# V2_0_1_KMX_Switch.net
KiCad netlist of a schematic drawn in EasyEDA Pro
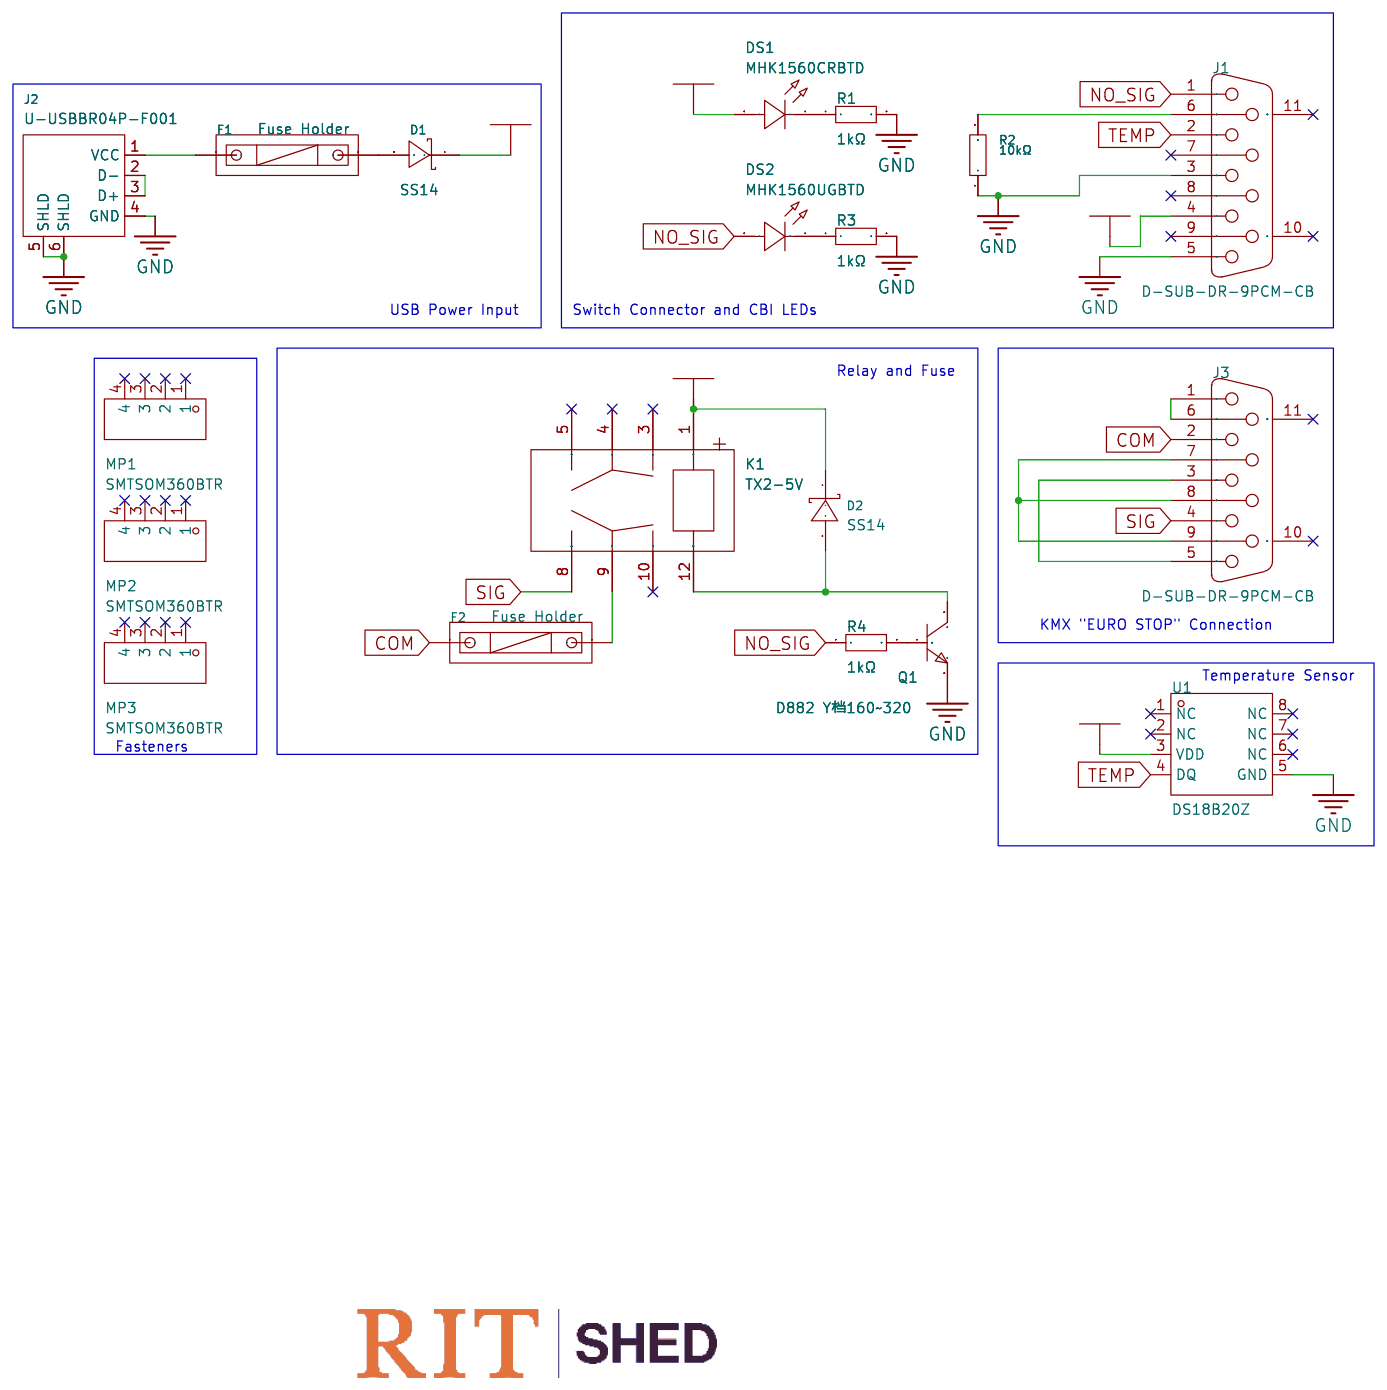
[diagram p0: schematic sheet]

(export (version "E")
  (design (tool "Eeschema 10.0.6"))
  (components
    (comp (ref "D1")
      (value "SS14")
      (footprint "easyedapro:SMA_L4.2-W2.6-LS5.3-RD")
      (fields (field (name "Manufacturer") "MDD"))
      (libsource (lib "easyedapro") (part "SS14"))
    )
    (comp (ref "D2")
      (value "SS14")
      (footprint "easyedapro:SMA_L4.2-W2.6-LS5.3-RD")
      (fields (field (name "Manufacturer") "MDD"))
      (libsource (lib "easyedapro") (part "SS14"))
    )
    (comp (ref "DS1")
      (value "MHK1560CRBTD")
      (footprint "easyedapro:LED-TH_MHK1560UGBTD")
      (fields (field (name "Manufacturer") "MEIHUA(美华)"))
      (libsource (lib "easyedapro") (part "MHK1560CGBTD"))
    )
    (comp (ref "DS2")
      (value "MHK1560UGBTD")
      (footprint "easyedapro:LED-TH_MHK1560UGBTD")
      (fields (field (name "Manufacturer") "MEIHUA(美华)"))
      (libsource (lib "easyedapro") (part "MHK1560UGBTD"))
    )
    (comp (ref "F1")
      (value "Fuse Holder")
      (footprint "easyedapro:FUSE-TH_L24.5-W9.8-P22.5")
      (description "Fuseholder Type:- Fuse Type:- Fuse Size:-")
      (fields (field (name "Manufacturer Part") "保险丝透明座") (field (name "Manufacturer") "xcfuse(旭程)"))
      (libsource (lib "easyedapro") (part "Fuse transparent seat"))
    )
    (comp (ref "F2")
      (value "Fuse Holder")
      (footprint "easyedapro:FUSE-TH_L24.5-W9.8-P22.5")
      (description "Fuseholder Type:- Fuse Type:- Fuse Size:-")
      (fields (field (name "Manufacturer Part") "保险丝透明座") (field (name "Manufacturer") "xcfuse(旭程)"))
      (libsource (lib "easyedapro") (part "Fuse transparent seat"))
    )
    (comp (ref "J1")
      (value "D-SUB-DR-9PCM-CB")
      (footprint "easyedapro:DB9-TH_ID09S33E4GV00LF")
      (fields (field (name "Manufacturer") "XUNPU(讯普)"))
      (libsource (lib "easyedapro") (part "D-SUB-DR-9PCM-CB"))
    )
    (comp (ref "J2")
      (value "U-USBBR04P-F001")
      (footprint "easyedapro:USB-B-TH_U241-041N-1BR85-1")
      (fields (field (name "Manufacturer") "Ckmtw(灿科盟)"))
      (libsource (lib "easyedapro") (part "U-USBBR04P-F001"))
    )
    (comp (ref "J3")
      (value "D-SUB-DR-9PCM-CB")
      (footprint "easyedapro:DB9-TH_ID09S33E4GV00LF")
      (fields (field (name "Manufacturer") "XUNPU(讯普)"))
      (libsource (lib "easyedapro") (part "D-SUB-DR-9PCM-CB"))
    )
    (comp (ref "K1")
      (value "TX2-5V")
      (footprint "easyedapro:RELAY-TH_TX2-3V")
      (fields (field (name "Manufacturer") "PANASONIC(松下)"))
      (libsource (lib "easyedapro") (part "TX2-5V"))
    )
    (comp (ref "MP1")
      (value "SMTSOM360BTR")
      (footprint "easyedapro:SMD_BD5.6-D4.1")
      (fields (field (name "Manufacturer") "YIYUAN(怡远)"))
      (libsource (lib "easyedapro") (part "SMTSOM360BTR"))
    )
    (comp (ref "MP2")
      (value "SMTSOM360BTR")
      (footprint "easyedapro:SMD_BD5.6-D4.1")
      (fields (field (name "Manufacturer") "YIYUAN(怡远)"))
      (libsource (lib "easyedapro") (part "SMTSOM360BTR"))
    )
    (comp (ref "MP3")
      (value "SMTSOM360BTR")
      (footprint "easyedapro:SMD_BD5.6-D4.1")
      (fields (field (name "Manufacturer") "YIYUAN(怡远)"))
      (libsource (lib "easyedapro") (part "SMTSOM360BTR"))
    )
    (comp (ref "Q1")
      (value "D882 Y档160~320")
      (footprint "easyedapro:SOT-89-3_L4.5-W2.5-P1.50-LS4.2-BR")
      (fields (field (name "Manufacturer") "CJ(江苏长电/长晶)"))
      (libsource (lib "easyedapro") (part "D882_C9634"))
    )
    (comp (ref "R1")
      (value "1kΩ")
      (footprint "easyedapro:R0805")
      (fields
        (field (name "Manufacturer Part") "0805W8F1001T5E")
        (field (name "Manufacturer") "UNI-ROYAL(厚声)")
      )
      (libsource (lib "easyedapro") (part "0805W8F1001T5E"))
    )
    (comp (ref "R2")
      (value "10kΩ")
      (footprint "easyedapro:R0805")
      (fields
        (field (name "Manufacturer Part") "0805W8F1002T5E")
        (field (name "Manufacturer") "UNI-ROYAL(厚声)")
      )
      (libsource (lib "easyedapro") (part "0805W8F1002T5E"))
    )
    (comp (ref "R3")
      (value "1kΩ")
      (footprint "easyedapro:R0805")
      (fields
        (field (name "Manufacturer Part") "0805W8F1001T5E")
        (field (name "Manufacturer") "UNI-ROYAL(厚声)")
      )
      (libsource (lib "easyedapro") (part "0805W8F1001T5E"))
    )
    (comp (ref "R4")
      (value "1kΩ")
      (footprint "easyedapro:R0805")
      (fields
        (field (name "Manufacturer Part") "0805W8F1001T5E")
        (field (name "Manufacturer") "UNI-ROYAL(厚声)")
      )
      (libsource (lib "easyedapro") (part "0805W8F1001T5E"))
    )
    (comp (ref "U1")
      (value "DS18B20Z")
      (footprint "easyedapro:SOP-8_L4.9-W3.9-P1.27-LS6.0-BL")
      (description "Resolution:±0.4°C Resolution:±0.4°C Supply Voltage:2.5V~5.5V Supply Voltage:2.5V~5.5V")
      (fields (field (name "Manufacturer") "UMW(友台半导体)"))
      (libsource (lib "easyedapro") (part "DS18B20Z"))
    )
  )
  (nets
    (net (code "1") (name "COM") (class "Default")
      (node (ref "F2") (pin "1") (pinfunction "1_1") (pintype "input"))
      (node (ref "J3") (pin "2") (pinfunction "2_2") (pintype "input"))
    )
    (net (code "2") (name "GND") (class "Default")
      (node (ref "J1") (pin "3") (pinfunction "3_3") (pintype "input"))
      (node (ref "J1") (pin "5") (pinfunction "5_5") (pintype "input"))
      (node (ref "J2") (pin "4") (pinfunction "GND_4") (pintype "input"))
      (node (ref "J2") (pin "5") (pinfunction "SHLD_5") (pintype "input"))
      (node (ref "J2") (pin "6") (pinfunction "SHLD_6") (pintype "input"))
      (node (ref "Q1") (pin "3") (pinfunction "E_3") (pintype "input"))
      (node (ref "R1") (pin "2") (pinfunction "2_2") (pintype "input"))
      (node (ref "R2") (pin "1") (pinfunction "1_1") (pintype "input"))
      (node (ref "R3") (pin "2") (pinfunction "2_2") (pintype "input"))
      (node (ref "U1") (pin "5") (pinfunction "GND_5") (pintype "unspecified"))
    )
    (net (code "3") (name "NO_SIG") (class "Default")
      (node (ref "DS2") (pin "2") (pinfunction "A_2") (pintype "unspecified"))
      (node (ref "J1") (pin "1") (pinfunction "1_1") (pintype "input"))
      (node (ref "R4") (pin "1") (pinfunction "1_1") (pintype "input"))
    )
    (net (code "4") (name "Net-(D1-A)") (class "Default")
      (node (ref "D1") (pin "2") (pinfunction "A_2") (pintype "input"))
      (node (ref "F1") (pin "2") (pinfunction "2_2") (pintype "input"))
    )
    (net (code "5") (name "Net-(D2-A)") (class "Default")
      (node (ref "D2") (pin "2") (pinfunction "A_2") (pintype "input"))
      (node (ref "K1") (pin "12") (pinfunction "12_12") (pintype "input"))
      (node (ref "Q1") (pin "2") (pinfunction "C_2") (pintype "input"))
    )
    (net (code "6") (name "Net-(DS1-K)") (class "Default")
      (node (ref "DS1") (pin "1") (pinfunction "K_1") (pintype "unspecified"))
      (node (ref "R1") (pin "1") (pinfunction "1_1") (pintype "input"))
    )
    (net (code "7") (name "Net-(DS2-K)") (class "Default")
      (node (ref "DS2") (pin "1") (pinfunction "K_1") (pintype "unspecified"))
      (node (ref "R3") (pin "1") (pinfunction "1_1") (pintype "input"))
    )
    (net (code "8") (name "Net-(F2-Pad2)") (class "Default")
      (node (ref "F2") (pin "2") (pinfunction "2_2") (pintype "input"))
      (node (ref "K1") (pin "9") (pinfunction "9_9") (pintype "input"))
    )
    (net (code "9") (name "Net-(J1-Pad6)") (class "Default")
      (node (ref "J1") (pin "6") (pinfunction "6_6") (pintype "input"))
      (node (ref "R2") (pin "2") (pinfunction "2_2") (pintype "input"))
    )
    (net (code "10") (name "Net-(J2-D+)") (class "Default")
      (node (ref "J2") (pin "2") (pinfunction "D-_2") (pintype "input"))
      (node (ref "J2") (pin "3") (pinfunction "D+_3") (pintype "input"))
    )
    (net (code "11") (name "Net-(J2-VCC)") (class "Default")
      (node (ref "F1") (pin "1") (pinfunction "1_1") (pintype "input"))
      (node (ref "J2") (pin "1") (pinfunction "VCC_1") (pintype "input"))
    )
    (net (code "12") (name "Net-(J3-Pad1)") (class "Default")
      (node (ref "J3") (pin "1") (pinfunction "1_1") (pintype "input"))
      (node (ref "J3") (pin "6") (pinfunction "6_6") (pintype "input"))
    )
    (net (code "13") (name "Net-(J3-Pad3)") (class "Default")
      (node (ref "J3") (pin "3") (pinfunction "3_3") (pintype "input"))
      (node (ref "J3") (pin "5") (pinfunction "5_5") (pintype "input"))
    )
    (net (code "14") (name "Net-(J3-Pad7)") (class "Default")
      (node (ref "J3") (pin "7") (pinfunction "7_7") (pintype "input"))
      (node (ref "J3") (pin "8") (pinfunction "8_8") (pintype "input"))
      (node (ref "J3") (pin "9") (pinfunction "9_9") (pintype "input"))
    )
    (net (code "15") (name "Net-(Q1-B)") (class "Default")
      (node (ref "Q1") (pin "1") (pinfunction "B_1") (pintype "input"))
      (node (ref "R4") (pin "2") (pinfunction "2_2") (pintype "input"))
    )
    (net (code "16") (name "SIG") (class "Default")
      (node (ref "J3") (pin "4") (pinfunction "4_4") (pintype "input"))
      (node (ref "K1") (pin "8") (pinfunction "8_8") (pintype "input"))
    )
    (net (code "17") (name "TEMP") (class "Default")
      (node (ref "J1") (pin "2") (pinfunction "2_2") (pintype "input"))
      (node (ref "U1") (pin "4") (pinfunction "DQ_4") (pintype "unspecified"))
    )
    (net (code "18") (name "VSW") (class "Default")
      (node (ref "D1") (pin "1") (pinfunction "K_1") (pintype "input"))
      (node (ref "D2") (pin "1") (pinfunction "K_1") (pintype "input"))
      (node (ref "DS1") (pin "2") (pinfunction "A_2") (pintype "unspecified"))
      (node (ref "J1") (pin "4") (pinfunction "4_4") (pintype "input"))
      (node (ref "K1") (pin "1") (pinfunction "1_1") (pintype "input"))
      (node (ref "U1") (pin "3") (pinfunction "VDD_3") (pintype "unspecified"))
    )
    (net (code "19") (name "unconnected-(J1-MH1-Pad10)") (class "Default")
      (node (ref "J1") (pin "10") (pinfunction "MH1_10") (pintype "input+no_connect"))
    )
    (net (code "20") (name "unconnected-(J1-MH2-Pad11)") (class "Default")
      (node (ref "J1") (pin "11") (pinfunction "MH2_11") (pintype "input+no_connect"))
    )
    (net (code "21") (name "unconnected-(J1-Pad7)") (class "Default")
      (node (ref "J1") (pin "7") (pinfunction "7_7") (pintype "input+no_connect"))
    )
    (net (code "22") (name "unconnected-(J1-Pad8)") (class "Default")
      (node (ref "J1") (pin "8") (pinfunction "8_8") (pintype "input+no_connect"))
    )
    (net (code "23") (name "unconnected-(J1-Pad9)") (class "Default")
      (node (ref "J1") (pin "9") (pinfunction "9_9") (pintype "input+no_connect"))
    )
    (net (code "24") (name "unconnected-(J3-MH1-Pad10)") (class "Default")
      (node (ref "J3") (pin "10") (pinfunction "MH1_10") (pintype "input+no_connect"))
    )
    (net (code "25") (name "unconnected-(J3-MH2-Pad11)") (class "Default")
      (node (ref "J3") (pin "11") (pinfunction "MH2_11") (pintype "input+no_connect"))
    )
    (net (code "26") (name "unconnected-(K1-Pad3)") (class "Default")
      (node (ref "K1") (pin "3") (pinfunction "3_3") (pintype "input+no_connect"))
    )
    (net (code "27") (name "unconnected-(K1-Pad4)") (class "Default")
      (node (ref "K1") (pin "4") (pinfunction "4_4") (pintype "input+no_connect"))
    )
    (net (code "28") (name "unconnected-(K1-Pad5)") (class "Default")
      (node (ref "K1") (pin "5") (pinfunction "5_5") (pintype "input+no_connect"))
    )
    (net (code "29") (name "unconnected-(K1-Pad10)") (class "Default")
      (node (ref "K1") (pin "10") (pinfunction "10_10") (pintype "input+no_connect"))
    )
    (net (code "30") (name "unconnected-(MP1-Pad1)") (class "Default")
      (node (ref "MP1") (pin "1") (pinfunction "1_1") (pintype "unspecified+no_connect"))
    )
    (net (code "31") (name "unconnected-(MP1-Pad2)") (class "Default")
      (node (ref "MP1") (pin "2") (pinfunction "2_2") (pintype "unspecified+no_connect"))
    )
    (net (code "32") (name "unconnected-(MP1-Pad3)") (class "Default")
      (node (ref "MP1") (pin "3") (pinfunction "3_3") (pintype "unspecified+no_connect"))
    )
    (net (code "33") (name "unconnected-(MP1-Pad4)") (class "Default")
      (node (ref "MP1") (pin "4") (pinfunction "4_4") (pintype "unspecified+no_connect"))
    )
    (net (code "34") (name "unconnected-(MP2-Pad1)") (class "Default")
      (node (ref "MP2") (pin "1") (pinfunction "1_1") (pintype "unspecified+no_connect"))
    )
    (net (code "35") (name "unconnected-(MP2-Pad2)") (class "Default")
      (node (ref "MP2") (pin "2") (pinfunction "2_2") (pintype "unspecified+no_connect"))
    )
    (net (code "36") (name "unconnected-(MP2-Pad3)") (class "Default")
      (node (ref "MP2") (pin "3") (pinfunction "3_3") (pintype "unspecified+no_connect"))
    )
    (net (code "37") (name "unconnected-(MP2-Pad4)") (class "Default")
      (node (ref "MP2") (pin "4") (pinfunction "4_4") (pintype "unspecified+no_connect"))
    )
    (net (code "38") (name "unconnected-(MP3-Pad1)") (class "Default")
      (node (ref "MP3") (pin "1") (pinfunction "1_1") (pintype "unspecified+no_connect"))
    )
    (net (code "39") (name "unconnected-(MP3-Pad2)") (class "Default")
      (node (ref "MP3") (pin "2") (pinfunction "2_2") (pintype "unspecified+no_connect"))
    )
    (net (code "40") (name "unconnected-(MP3-Pad3)") (class "Default")
      (node (ref "MP3") (pin "3") (pinfunction "3_3") (pintype "unspecified+no_connect"))
    )
    (net (code "41") (name "unconnected-(MP3-Pad4)") (class "Default")
      (node (ref "MP3") (pin "4") (pinfunction "4_4") (pintype "unspecified+no_connect"))
    )
    (net (code "42") (name "unconnected-(U1-NC-Pad1)") (class "Default")
      (node (ref "U1") (pin "1") (pinfunction "NC_1") (pintype "unspecified+no_connect"))
    )
    (net (code "43") (name "unconnected-(U1-NC-Pad2)") (class "Default")
      (node (ref "U1") (pin "2") (pinfunction "NC_2") (pintype "unspecified+no_connect"))
    )
    (net (code "44") (name "unconnected-(U1-NC-Pad6)") (class "Default")
      (node (ref "U1") (pin "6") (pinfunction "NC_6") (pintype "unspecified+no_connect"))
    )
    (net (code "45") (name "unconnected-(U1-NC-Pad7)") (class "Default")
      (node (ref "U1") (pin "7") (pinfunction "NC_7") (pintype "unspecified+no_connect"))
    )
    (net (code "46") (name "unconnected-(U1-NC-Pad8)") (class "Default")
      (node (ref "U1") (pin "8") (pinfunction "NC_8") (pintype "unspecified+no_connect"))
    )
  )
)
